# balancingrobot.net
KiCad netlist of a schematic drawn in Altium Designer
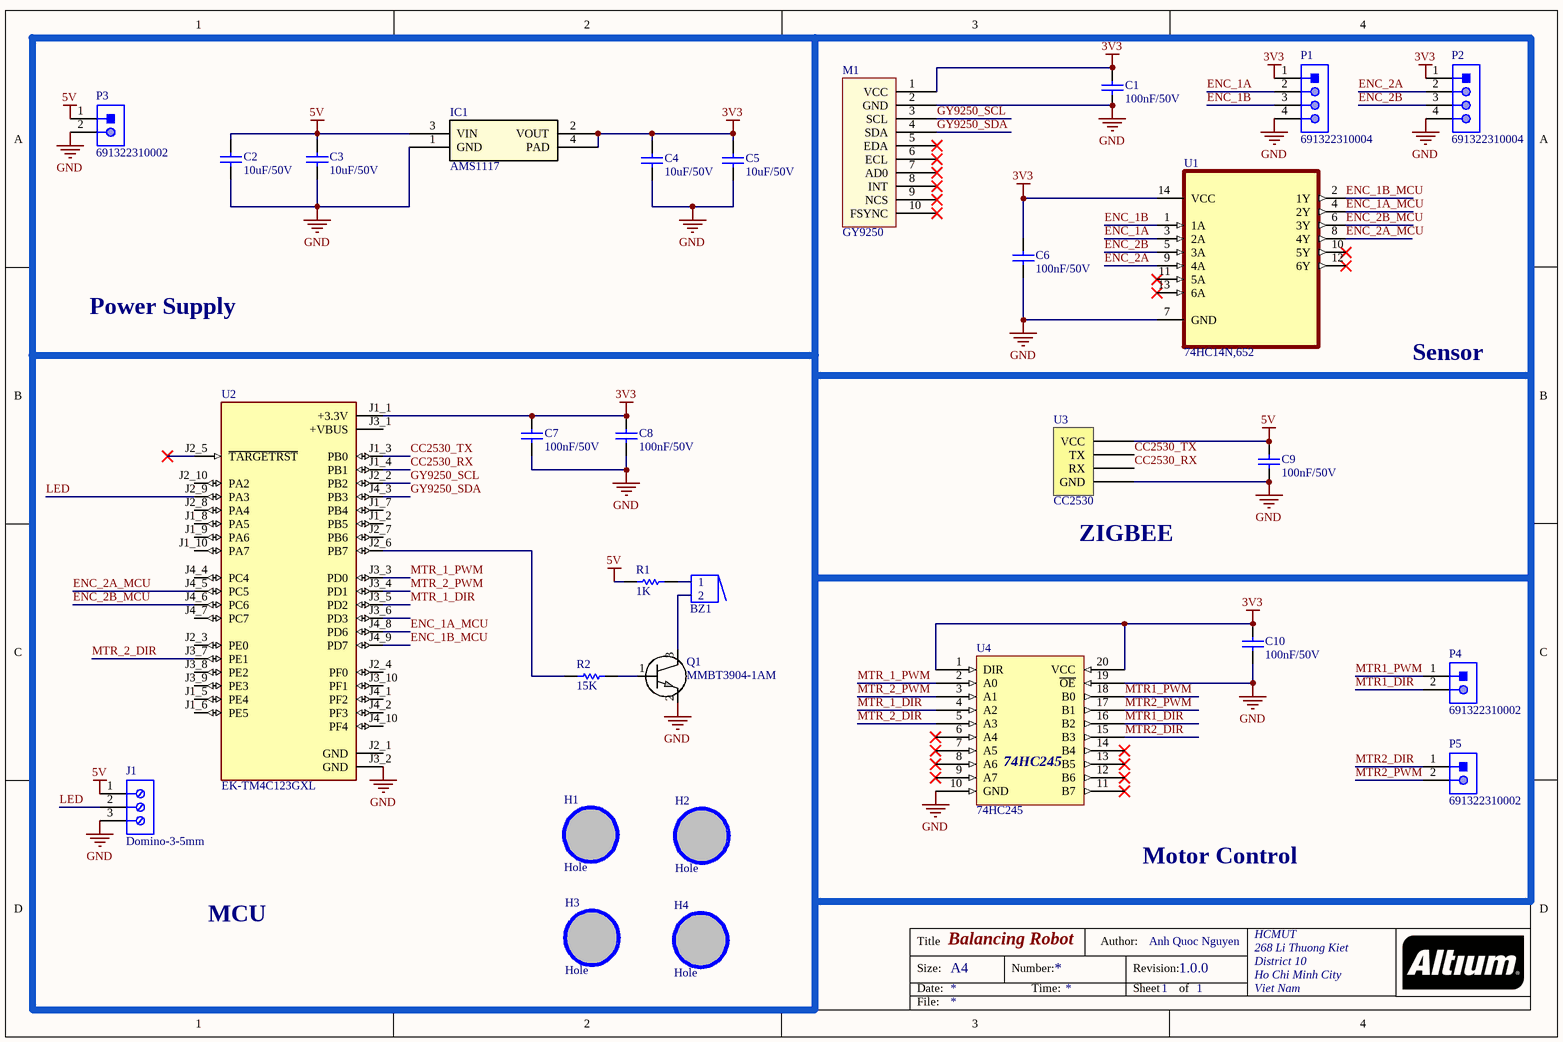
[diagram p0: balancingrobot.SchDoc]

(export (version "E")
  (design (tool "Eeschema 10.0.6"))
  (components
    (comp (ref "BZ1") (value "Buzzer") (footprint "BUZZER") (libsource (lib "xecanbang") (part "Buzzer")))
    (comp (ref "C1")
      (value "100nF/50V")
      (footprint "CAP-SM-0805")
      (description "CAP CER 0.1UF 50V Y5V 0805")
      (fields
        (field (name "MANUFACTURER") "Samsung Electro-Mechanics")
        (field (name "MANUFACTURER PART NUMBER") "CL21F104ZBCNNNC")
      )
      (libsource (lib "Capacitor") (part "Cap-100nF-50V-0805"))
    )
    (comp (ref "C2")
      (value "10uF/50V")
      (footprint "CAP-SM-0805")
      (description "CAP CER 10UF 50V X5R 0805")
      (fields
        (field (name "MANUFACTURER") "Yageo")
        (field (name "MANUFACTURER PART NUMBER") "CC0805KKX5R9BB106")
      )
      (libsource (lib "Capacitor") (part "Cap-10uF-50V-0805"))
    )
    (comp (ref "C3")
      (value "10uF/50V")
      (footprint "CAP-SM-0805")
      (description "CAP CER 10UF 50V X5R 0805")
      (fields
        (field (name "MANUFACTURER") "Yageo")
        (field (name "MANUFACTURER PART NUMBER") "CC0805KKX5R9BB106")
      )
      (libsource (lib "Capacitor") (part "Cap-10uF-50V-0805"))
    )
    (comp (ref "C4")
      (value "10uF/50V")
      (footprint "CAP-SM-0805")
      (description "CAP CER 10UF 50V X5R 0805")
      (fields
        (field (name "MANUFACTURER") "Yageo")
        (field (name "MANUFACTURER PART NUMBER") "CC0805KKX5R9BB106")
      )
      (libsource (lib "Capacitor") (part "Cap-10uF-50V-0805"))
    )
    (comp (ref "C5")
      (value "10uF/50V")
      (footprint "CAP-SM-0805")
      (description "CAP CER 10UF 50V X5R 0805")
      (fields
        (field (name "MANUFACTURER") "Yageo")
        (field (name "MANUFACTURER PART NUMBER") "CC0805KKX5R9BB106")
      )
      (libsource (lib "Capacitor") (part "Cap-10uF-50V-0805"))
    )
    (comp (ref "C6")
      (value "100nF/50V")
      (footprint "CAP-SM-0805")
      (description "CAP CER 0.1UF 50V Y5V 0805")
      (fields
        (field (name "MANUFACTURER") "Samsung Electro-Mechanics")
        (field (name "MANUFACTURER PART NUMBER") "CL21F104ZBCNNNC")
      )
      (libsource (lib "Capacitor") (part "Cap-100nF-50V-0805"))
    )
    (comp (ref "C7")
      (value "100nF/50V")
      (footprint "CAP-SM-0805")
      (description "CAP CER 0.1UF 50V Y5V 0805")
      (fields
        (field (name "MANUFACTURER") "Samsung Electro-Mechanics")
        (field (name "MANUFACTURER PART NUMBER") "CL21F104ZBCNNNC")
      )
      (libsource (lib "Capacitor") (part "Cap-100nF-50V-0805"))
    )
    (comp (ref "C8")
      (value "100nF/50V")
      (footprint "CAP-SM-0805")
      (description "CAP CER 0.1UF 50V Y5V 0805")
      (fields
        (field (name "MANUFACTURER") "Samsung Electro-Mechanics")
        (field (name "MANUFACTURER PART NUMBER") "CL21F104ZBCNNNC")
      )
      (libsource (lib "Capacitor") (part "Cap-100nF-50V-0805"))
    )
    (comp (ref "C9")
      (value "100nF/50V")
      (footprint "CAP-SM-0805")
      (description "CAP CER 0.1UF 50V Y5V 0805")
      (fields
        (field (name "MANUFACTURER") "Samsung Electro-Mechanics")
        (field (name "MANUFACTURER PART NUMBER") "CL21F104ZBCNNNC")
      )
      (libsource (lib "Capacitor") (part "Cap-100nF-50V-0805"))
    )
    (comp (ref "C10")
      (value "100nF/50V")
      (footprint "CAP-SM-0805")
      (description "CAP CER 0.1UF 50V Y5V 0805")
      (fields
        (field (name "MANUFACTURER") "Samsung Electro-Mechanics")
        (field (name "MANUFACTURER PART NUMBER") "CL21F104ZBCNNNC")
      )
      (libsource (lib "Capacitor") (part "Cap-100nF-50V-0805"))
    )
    (comp (ref "H1")
      (value "Hole")
      (footprint "LO KHOAN 3MM")
      (description "Hole 3mm")
      (libsource (lib "PIF_C16_lib") (part "Hole"))
    )
    (comp (ref "H2")
      (value "Hole")
      (footprint "LO KHOAN 3MM")
      (description "Hole 3mm")
      (libsource (lib "PIF_C16_lib") (part "Hole"))
    )
    (comp (ref "H3")
      (value "Hole")
      (footprint "LO KHOAN 3MM")
      (description "Hole 3mm")
      (libsource (lib "PIF_C16_lib") (part "Hole"))
    )
    (comp (ref "H4")
      (value "Hole")
      (footprint "LO KHOAN 3MM")
      (description "Hole 3mm")
      (libsource (lib "PIF_C16_lib") (part "Hole"))
    )
    (comp (ref "IC1")
      (value "AMS1117")
      (footprint "SOT223_AMS111700")
      (fields
        (field (name "MANUFACTURER_PART_NUMBER") "AMS1117-5.0")
        (field (name "COPYRIGHT") "Copyright (C) 2018 Accelerated Designs. All rights reserved")
      )
      (libsource (lib "balancing") (part "AMS1117"))
    )
    (comp (ref "J1")
      (value "Domino-3-5mm")
      (footprint "DOMINO-3-5mm")
      (description "WR-TBL Serie 1347 Horizontal Cable Entry, Pressure Clamp, pitch 5mm, 3p")
      (fields (field (name "PART NUMBER") "691134710003") (field (name "PUBLISHER") "Wurth Elektronik"))
      (libsource (lib "Header-connector") (part "Domino-3-5mm"))
    )
    (comp (ref "M1") (value "GY9250") (footprint "GY9250") (libsource (lib "balancing") (part "GY9250")))
    (comp (ref "P1")
      (value "691322310004")
      (footprint "691322310004")
      (description "WR-TBL Serie 322 Horizontal PCB Header, Pluggable, pitch 3.81mm, 4p")
      (fields (field (name "PUBLISHER") "Wurth Elektronik"))
      (libsource (lib "691322310002.") (part "691322310004"))
    )
    (comp (ref "P2")
      (value "691322310004")
      (footprint "691322310004")
      (description "WR-TBL Serie 322 Horizontal PCB Header, Pluggable, pitch 3.81mm, 4p")
      (fields (field (name "PUBLISHER") "Wurth Elektronik"))
      (libsource (lib "691322310002.") (part "691322310004"))
    )
    (comp (ref "P3")
      (value "691322310002")
      (footprint "691322310002")
      (description "WR-TBL Serie 322 Horizontal PCB Header, Pluggable, pitch 3.81mm, 2p")
      (fields (field (name "PUBLISHER") "Wurth Elektronik"))
      (libsource (lib "691322310002.") (part "691322310002"))
    )
    (comp (ref "P4")
      (value "691322310002")
      (footprint "691322310002")
      (description "WR-TBL Serie 322 Horizontal PCB Header, Pluggable, pitch 3.81mm, 2p")
      (fields (field (name "PUBLISHER") "Wurth Elektronik"))
      (libsource (lib "691322310002.") (part "691322310002"))
    )
    (comp (ref "P5")
      (value "691322310002")
      (footprint "691322310002")
      (description "WR-TBL Serie 322 Horizontal PCB Header, Pluggable, pitch 3.81mm, 2p")
      (fields (field (name "PUBLISHER") "Wurth Elektronik"))
      (libsource (lib "691322310002.") (part "691322310002"))
    )
    (comp (ref "Q1")
      (value "MMBT3904-1AM")
      (footprint "SOT23_NEX")
      (fields
        (field (name "MANUFACTURER_PART_NUMBER") "MMBT3904")
        (field (name "COPYRIGHT") "Copyright (C) 2016 Accelerated Designs. All rights reserved")
      )
      (libsource (lib "xecanbang") (part "MMBT3904-1AM"))
    )
    (comp (ref "R1")
      (value "1K")
      (footprint "Resistor:RES-SM-0805")
      (description "RES 1K OHM 1% 1/4W 0805")
      (fields
        (field (name "MANUFACTURER") "Stackpole Electronics Inc")
        (field (name "MANUFACTURER PART NUMBER") "RNCP0805FTD1K00")
      )
      (libsource (lib "Resistor") (part "Res-1K-0805"))
    )
    (comp (ref "R2")
      (value "15K")
      (footprint "Resistor:RES-SM-0805")
      (description "RES 15K OHM 1% 1/4W 0805")
      (fields
        (field (name "MANUFACTURER") "TE Connectivity Passive Product")
        (field (name "MANUFACTURER PART NUMBER") "CRGCQ0805F15K")
      )
      (libsource (lib "Resistor") (part "Res-15K-0805"))
    )
    (comp (ref "U1")
      (value "74HC14N,652")
      (footprint "DIP254P762X420-14")
      (description "Inverter IC 6 Channel Schmitt Trigger 14-DIP")
      (fields (field (name "MF") "NXP USA"))
      (libsource (lib "74HC14N_652") (part "74HC14N,652"))
    )
    (comp (ref "U2")
      (value "EK-TM4C123GXL")
      (footprint "MODULE_EK-TM4C123GXL")
      (description "ARMÂ® CortexÂ®-M4F Based MCU TM4C123G LaunchPadâ„¢ Evaluation Kit")
      (fields (field (name "MF") "Texas Instruments"))
      (libsource (lib "balancing") (part "EK-TM4C123GXL"))
    )
    (comp (ref "U3")
      (value "CC2530")
      (footprint "CC2530")
      (description "Zigbee")
      (libsource (lib "balancing") (part "Zigbee CC2530"))
    )
    (comp (ref "U4")
      (value "74HC245")
      (footprint "dip20")
      (description "Dán")
      (libsource (lib "THU VIEN SCH") (part "74HC245"))
    )
  )
  (nets
    (net (code "1") (name "/CC2530_RX") (class "Default")
      (node (ref "U2") (pin "J1_4") (pinfunction "PB1_J1_4") (pintype "bidirectional"))
      (node (ref "U3") (pin "3") (pinfunction "RX_3") (pintype "passive"))
    )
    (net (code "2") (name "/CC2530_TX") (class "Default")
      (node (ref "U2") (pin "J1_3") (pinfunction "PB0_J1_3") (pintype "bidirectional"))
      (node (ref "U3") (pin "2") (pinfunction "TX_2") (pintype "passive"))
    )
    (net (code "3") (name "/ENC_1A") (class "Default")
      (node (ref "P1") (pin "2") (pinfunction "2_2") (pintype "passive"))
      (node (ref "U1") (pin "3") (pinfunction "2A_3") (pintype "input"))
    )
    (net (code "4") (name "/ENC_1A_MCU") (class "Default")
      (node (ref "U1") (pin "4") (pinfunction "2Y_4") (pintype "output"))
      (node (ref "U2") (pin "J4_8") (pinfunction "PD6_J4_8") (pintype "bidirectional"))
    )
    (net (code "5") (name "/ENC_1B") (class "Default")
      (node (ref "P1") (pin "3") (pinfunction "3_3") (pintype "passive"))
      (node (ref "U1") (pin "1") (pinfunction "1A_1") (pintype "input"))
    )
    (net (code "6") (name "/ENC_1B_MCU") (class "Default")
      (node (ref "U1") (pin "2") (pinfunction "1Y_2") (pintype "output"))
      (node (ref "U2") (pin "J4_9") (pinfunction "PD7_J4_9") (pintype "bidirectional"))
    )
    (net (code "7") (name "/ENC_2A") (class "Default")
      (node (ref "P2") (pin "2") (pinfunction "2_2") (pintype "passive"))
      (node (ref "U1") (pin "9") (pinfunction "4A_9") (pintype "input"))
    )
    (net (code "8") (name "/ENC_2A_MCU") (class "Default")
      (node (ref "U1") (pin "8") (pinfunction "4Y_8") (pintype "output"))
      (node (ref "U2") (pin "J4_5") (pinfunction "PC5_J4_5") (pintype "bidirectional"))
    )
    (net (code "9") (name "/ENC_2B") (class "Default")
      (node (ref "P2") (pin "3") (pinfunction "3_3") (pintype "passive"))
      (node (ref "U1") (pin "5") (pinfunction "3A_5") (pintype "input"))
    )
    (net (code "10") (name "/ENC_2B_MCU") (class "Default")
      (node (ref "U1") (pin "6") (pinfunction "3Y_6") (pintype "output"))
      (node (ref "U2") (pin "J4_6") (pinfunction "PC6_J4_6") (pintype "bidirectional"))
    )
    (net (code "11") (name "/GY9250_SCL") (class "Default")
      (node (ref "M1") (pin "3") (pinfunction "SCL_3") (pintype "passive"))
      (node (ref "U2") (pin "J2_2") (pinfunction "PB2_J2_2") (pintype "bidirectional"))
    )
    (net (code "12") (name "/GY9250_SDA") (class "Default")
      (node (ref "M1") (pin "4") (pinfunction "SDA_4") (pintype "passive"))
      (node (ref "U2") (pin "J4_3") (pinfunction "PB3_J4_3") (pintype "bidirectional"))
    )
    (net (code "13") (name "/LED") (class "Default")
      (node (ref "J1") (pin "2") (pinfunction "2_2") (pintype "passive"))
      (node (ref "U2") (pin "J2_9") (pinfunction "PA3_J2_9") (pintype "bidirectional"))
    )
    (net (code "14") (name "/MTR1_DIR") (class "Default")
      (node (ref "P4") (pin "2") (pinfunction "2_2") (pintype "passive"))
      (node (ref "U4") (pin "16") (pinfunction "B2_16") (pintype "output"))
    )
    (net (code "15") (name "/MTR1_PWM") (class "Default")
      (node (ref "P4") (pin "1") (pinfunction "1_1") (pintype "passive"))
      (node (ref "U4") (pin "18") (pinfunction "B0_18") (pintype "output"))
    )
    (net (code "16") (name "/MTR2_DIR") (class "Default")
      (node (ref "P5") (pin "1") (pinfunction "1_1") (pintype "passive"))
      (node (ref "U4") (pin "15") (pinfunction "B3_15") (pintype "output"))
    )
    (net (code "17") (name "/MTR2_PWM") (class "Default")
      (node (ref "P5") (pin "2") (pinfunction "2_2") (pintype "passive"))
      (node (ref "U4") (pin "17") (pinfunction "B1_17") (pintype "output"))
    )
    (net (code "18") (name "/MTR_1_DIR") (class "Default")
      (node (ref "U2") (pin "J3_5") (pinfunction "PD2_J3_5") (pintype "bidirectional"))
      (node (ref "U4") (pin "4") (pinfunction "A2_4") (pintype "input"))
    )
    (net (code "19") (name "/MTR_1_PWM") (class "Default")
      (node (ref "U2") (pin "J3_3") (pinfunction "PD0_J3_3") (pintype "bidirectional"))
      (node (ref "U4") (pin "2") (pinfunction "A0_2") (pintype "input"))
    )
    (net (code "20") (name "/MTR_2_DIR") (class "Default")
      (node (ref "U2") (pin "J3_7") (pinfunction "PE1_J3_7") (pintype "bidirectional"))
      (node (ref "U4") (pin "5") (pinfunction "A3_5") (pintype "input"))
    )
    (net (code "21") (name "/MTR_2_PWM") (class "Default")
      (node (ref "U2") (pin "J3_4") (pinfunction "PD1_J3_4") (pintype "bidirectional"))
      (node (ref "U4") (pin "3") (pinfunction "A1_3") (pintype "input"))
    )
    (net (code "22") (name "3V3") (class "Default")
      (node (ref "C1") (pin "2") (pinfunction "2_2") (pintype "passive"))
      (node (ref "C10") (pin "2") (pinfunction "2_2") (pintype "passive"))
      (node (ref "C4") (pin "2") (pinfunction "2_2") (pintype "passive"))
      (node (ref "C5") (pin "2") (pinfunction "2_2") (pintype "passive"))
      (node (ref "C6") (pin "2") (pinfunction "2_2") (pintype "passive"))
      (node (ref "C7") (pin "2") (pinfunction "2_2") (pintype "passive"))
      (node (ref "C8") (pin "2") (pinfunction "2_2") (pintype "passive"))
      (node (ref "IC1") (pin "2") (pinfunction "VOUT_2") (pintype "passive"))
      (node (ref "IC1") (pin "4") (pinfunction "PAD_4") (pintype "passive"))
      (node (ref "M1") (pin "1") (pinfunction "VCC_1") (pintype "passive"))
      (node (ref "P1") (pin "1") (pinfunction "1_1") (pintype "passive"))
      (node (ref "P2") (pin "1") (pinfunction "1_1") (pintype "passive"))
      (node (ref "U1") (pin "14") (pinfunction "VCC_14") (pintype "power_in"))
      (node (ref "U2") (pin "J1_1") (pinfunction "+3.3V_J1_1") (pintype "power_in"))
      (node (ref "U4") (pin "1") (pinfunction "DIR_1") (pintype "input"))
      (node (ref "U4") (pin "20") (pinfunction "VCC_20") (pintype "input"))
    )
    (net (code "23") (name "5V") (class "Default")
      (node (ref "C2") (pin "2") (pinfunction "2_2") (pintype "passive"))
      (node (ref "C3") (pin "2") (pinfunction "2_2") (pintype "passive"))
      (node (ref "C9") (pin "2") (pinfunction "2_2") (pintype "passive"))
      (node (ref "IC1") (pin "3") (pinfunction "VIN_3") (pintype "passive"))
      (node (ref "J1") (pin "1") (pinfunction "1_1") (pintype "passive"))
      (node (ref "P3") (pin "1") (pinfunction "1_1") (pintype "passive"))
      (node (ref "R1") (pin "2") (pinfunction "2_2") (pintype "passive"))
      (node (ref "U3") (pin "1") (pinfunction "VCC_1") (pintype "passive"))
    )
    (net (code "24") (name "GND") (class "Default")
      (node (ref "C1") (pin "1") (pinfunction "1_1") (pintype "passive"))
      (node (ref "C10") (pin "1") (pinfunction "1_1") (pintype "passive"))
      (node (ref "C2") (pin "1") (pinfunction "1_1") (pintype "passive"))
      (node (ref "C3") (pin "1") (pinfunction "1_1") (pintype "passive"))
      (node (ref "C4") (pin "1") (pinfunction "1_1") (pintype "passive"))
      (node (ref "C5") (pin "1") (pinfunction "1_1") (pintype "passive"))
      (node (ref "C6") (pin "1") (pinfunction "1_1") (pintype "passive"))
      (node (ref "C7") (pin "1") (pinfunction "1_1") (pintype "passive"))
      (node (ref "C8") (pin "1") (pinfunction "1_1") (pintype "passive"))
      (node (ref "C9") (pin "1") (pinfunction "1_1") (pintype "passive"))
      (node (ref "IC1") (pin "1") (pinfunction "GND_1") (pintype "passive"))
      (node (ref "J1") (pin "3") (pinfunction "3_3") (pintype "passive"))
      (node (ref "M1") (pin "2") (pinfunction "GND_2") (pintype "passive"))
      (node (ref "P1") (pin "4") (pinfunction "4_4") (pintype "passive"))
      (node (ref "P2") (pin "4") (pinfunction "4_4") (pintype "passive"))
      (node (ref "P3") (pin "2") (pinfunction "2_2") (pintype "passive"))
      (node (ref "Q1") (pin "2") (pinfunction "2_2") (pintype "passive"))
      (node (ref "U1") (pin "7") (pinfunction "GND_7") (pintype "passive"))
      (node (ref "U2") (pin "J3_2") (pinfunction "GND_J3_2") (pintype "power_in"))
      (node (ref "U3") (pin "4") (pinfunction "GND_4") (pintype "passive"))
      (node (ref "U4") (pin "10") (pinfunction "GND_10") (pintype "input"))
      (node (ref "U4") (pin "19") (pinfunction "~{OE}_19") (pintype "input"))
    )
    (net (code "25") (name "Net-(BZ1-Pad1)") (class "Default")
      (node (ref "BZ1") (pin "1") (pinfunction "1_1") (pintype "passive"))
      (node (ref "R1") (pin "1") (pinfunction "1_1") (pintype "passive"))
    )
    (net (code "26") (name "Net-(BZ1-Pad2)") (class "Default")
      (node (ref "BZ1") (pin "2") (pinfunction "2_2") (pintype "passive"))
      (node (ref "Q1") (pin "3") (pinfunction "3_3") (pintype "passive"))
    )
    (net (code "27") (name "Net-(Q1-Pad1)") (class "Default")
      (node (ref "Q1") (pin "1") (pinfunction "1_1") (pintype "passive"))
      (node (ref "R2") (pin "2") (pinfunction "2_2") (pintype "passive"))
    )
    (net (code "28") (name "Net-(U2-PB7)") (class "Default")
      (node (ref "R2") (pin "1") (pinfunction "1_1") (pintype "passive"))
      (node (ref "U2") (pin "J2_6") (pinfunction "PB7_J2_6") (pintype "bidirectional"))
    )
    (net (code "29") (name "unconnected-(H1-Pad1)") (class "Default")
      (node (ref "H1") (pin "1") (pinfunction "1_1") (pintype "passive"))
    )
    (net (code "30") (name "unconnected-(H2-Pad1)") (class "Default")
      (node (ref "H2") (pin "1") (pinfunction "1_1") (pintype "passive"))
    )
    (net (code "31") (name "unconnected-(H3-Pad1)") (class "Default")
      (node (ref "H3") (pin "1") (pinfunction "1_1") (pintype "passive"))
    )
    (net (code "32") (name "unconnected-(H4-Pad1)") (class "Default")
      (node (ref "H4") (pin "1") (pinfunction "1_1") (pintype "passive"))
    )
    (net (code "33") (name "unconnected-(M1-AD0-Pad7)") (class "Default")
      (node (ref "M1") (pin "7") (pinfunction "AD0_7") (pintype "passive+no_connect"))
    )
    (net (code "34") (name "unconnected-(M1-ECL-Pad6)") (class "Default")
      (node (ref "M1") (pin "6") (pinfunction "ECL_6") (pintype "passive+no_connect"))
    )
    (net (code "35") (name "unconnected-(M1-EDA-Pad5)") (class "Default")
      (node (ref "M1") (pin "5") (pinfunction "EDA_5") (pintype "passive+no_connect"))
    )
    (net (code "36") (name "unconnected-(M1-FSYNC-Pad10)") (class "Default")
      (node (ref "M1") (pin "10") (pinfunction "FSYNC_10") (pintype "passive+no_connect"))
    )
    (net (code "37") (name "unconnected-(M1-INT-Pad8)") (class "Default")
      (node (ref "M1") (pin "8") (pinfunction "INT_8") (pintype "passive+no_connect"))
    )
    (net (code "38") (name "unconnected-(M1-NCS-Pad9)") (class "Default")
      (node (ref "M1") (pin "9") (pinfunction "NCS_9") (pintype "passive+no_connect"))
    )
    (net (code "39") (name "unconnected-(U1-5A-Pad11)") (class "Default")
      (node (ref "U1") (pin "11") (pinfunction "5A_11") (pintype "input+no_connect"))
    )
    (net (code "40") (name "unconnected-(U1-5Y-Pad10)") (class "Default")
      (node (ref "U1") (pin "10") (pinfunction "5Y_10") (pintype "output+no_connect"))
    )
    (net (code "41") (name "unconnected-(U1-6A-Pad13)") (class "Default")
      (node (ref "U1") (pin "13") (pinfunction "6A_13") (pintype "input+no_connect"))
    )
    (net (code "42") (name "unconnected-(U1-6Y-Pad12)") (class "Default")
      (node (ref "U1") (pin "12") (pinfunction "6Y_12") (pintype "output+no_connect"))
    )
    (net (code "43") (name "unconnected-(U2-+VBUS-PadJ3_1)") (class "Default")
      (node (ref "U2") (pin "J3_1") (pinfunction "+VBUS_J3_1") (pintype "power_in"))
    )
    (net (code "44") (name "unconnected-(U2-GND-PadJ2_1)") (class "Default")
      (node (ref "U2") (pin "J2_1") (pinfunction "GND_J2_1") (pintype "power_in"))
    )
    (net (code "45") (name "unconnected-(U2-PA2-PadJ2_10)") (class "Default")
      (node (ref "U2") (pin "J2_10") (pinfunction "PA2_J2_10") (pintype "bidirectional"))
    )
    (net (code "46") (name "unconnected-(U2-PA4-PadJ2_8)") (class "Default")
      (node (ref "U2") (pin "J2_8") (pinfunction "PA4_J2_8") (pintype "bidirectional"))
    )
    (net (code "47") (name "unconnected-(U2-PA5-PadJ1_8)") (class "Default")
      (node (ref "U2") (pin "J1_8") (pinfunction "PA5_J1_8") (pintype "bidirectional"))
    )
    (net (code "48") (name "unconnected-(U2-PA6-PadJ1_9)") (class "Default")
      (node (ref "U2") (pin "J1_9") (pinfunction "PA6_J1_9") (pintype "bidirectional"))
    )
    (net (code "49") (name "unconnected-(U2-PA7-PadJ1_10)") (class "Default")
      (node (ref "U2") (pin "J1_10") (pinfunction "PA7_J1_10") (pintype "bidirectional"))
    )
    (net (code "50") (name "unconnected-(U2-PB4-PadJ1_7)") (class "Default")
      (node (ref "U2") (pin "J1_7") (pinfunction "PB4_J1_7") (pintype "bidirectional"))
    )
    (net (code "51") (name "unconnected-(U2-PB5-PadJ1_2)") (class "Default")
      (node (ref "U2") (pin "J1_2") (pinfunction "PB5_J1_2") (pintype "bidirectional"))
    )
    (net (code "52") (name "unconnected-(U2-PB6-PadJ2_7)") (class "Default")
      (node (ref "U2") (pin "J2_7") (pinfunction "PB6_J2_7") (pintype "bidirectional"))
    )
    (net (code "53") (name "unconnected-(U2-PC4-PadJ4_4)") (class "Default")
      (node (ref "U2") (pin "J4_4") (pinfunction "PC4_J4_4") (pintype "bidirectional"))
    )
    (net (code "54") (name "unconnected-(U2-PC7-PadJ4_7)") (class "Default")
      (node (ref "U2") (pin "J4_7") (pinfunction "PC7_J4_7") (pintype "bidirectional"))
    )
    (net (code "55") (name "unconnected-(U2-PD3-PadJ3_6)") (class "Default")
      (node (ref "U2") (pin "J3_6") (pinfunction "PD3_J3_6") (pintype "bidirectional"))
    )
    (net (code "56") (name "unconnected-(U2-PE0-PadJ2_3)") (class "Default")
      (node (ref "U2") (pin "J2_3") (pinfunction "PE0_J2_3") (pintype "bidirectional"))
    )
    (net (code "57") (name "unconnected-(U2-PE2-PadJ3_8)") (class "Default")
      (node (ref "U2") (pin "J3_8") (pinfunction "PE2_J3_8") (pintype "bidirectional"))
    )
    (net (code "58") (name "unconnected-(U2-PE3-PadJ3_9)") (class "Default")
      (node (ref "U2") (pin "J3_9") (pinfunction "PE3_J3_9") (pintype "bidirectional"))
    )
    (net (code "59") (name "unconnected-(U2-PE4-PadJ1_5)") (class "Default")
      (node (ref "U2") (pin "J1_5") (pinfunction "PE4_J1_5") (pintype "bidirectional"))
    )
    (net (code "60") (name "unconnected-(U2-PE5-PadJ1_6)") (class "Default")
      (node (ref "U2") (pin "J1_6") (pinfunction "PE5_J1_6") (pintype "bidirectional"))
    )
    (net (code "61") (name "unconnected-(U2-PF0-PadJ2_4)") (class "Default")
      (node (ref "U2") (pin "J2_4") (pinfunction "PF0_J2_4") (pintype "bidirectional"))
    )
    (net (code "62") (name "unconnected-(U2-PF1-PadJ3_10)") (class "Default")
      (node (ref "U2") (pin "J3_10") (pinfunction "PF1_J3_10") (pintype "bidirectional"))
    )
    (net (code "63") (name "unconnected-(U2-PF2-PadJ4_1)") (class "Default")
      (node (ref "U2") (pin "J4_1") (pinfunction "PF2_J4_1") (pintype "bidirectional"))
    )
    (net (code "64") (name "unconnected-(U2-PF3-PadJ4_2)") (class "Default")
      (node (ref "U2") (pin "J4_2") (pinfunction "PF3_J4_2") (pintype "bidirectional"))
    )
    (net (code "65") (name "unconnected-(U2-PF4-PadJ4_10)") (class "Default")
      (node (ref "U2") (pin "J4_10") (pinfunction "PF4_J4_10") (pintype "bidirectional"))
    )
    (net (code "66") (name "unconnected-(U2-~{TARGETRST}-PadJ2_5)") (class "Default")
      (node (ref "U2") (pin "J2_5") (pinfunction "~{TARGETRST}_J2_5") (pintype "input+no_connect"))
    )
    (net (code "67") (name "unconnected-(U4-A4-Pad6)") (class "Default")
      (node (ref "U4") (pin "6") (pinfunction "A4_6") (pintype "input+no_connect"))
    )
    (net (code "68") (name "unconnected-(U4-A5-Pad7)") (class "Default")
      (node (ref "U4") (pin "7") (pinfunction "A5_7") (pintype "input+no_connect"))
    )
    (net (code "69") (name "unconnected-(U4-A6-Pad8)") (class "Default")
      (node (ref "U4") (pin "8") (pinfunction "A6_8") (pintype "input+no_connect"))
    )
    (net (code "70") (name "unconnected-(U4-A7-Pad9)") (class "Default")
      (node (ref "U4") (pin "9") (pinfunction "A7_9") (pintype "input+no_connect"))
    )
    (net (code "71") (name "unconnected-(U4-B4-Pad14)") (class "Default")
      (node (ref "U4") (pin "14") (pinfunction "B4_14") (pintype "output+no_connect"))
    )
    (net (code "72") (name "unconnected-(U4-B5-Pad13)") (class "Default")
      (node (ref "U4") (pin "13") (pinfunction "B5_13") (pintype "output+no_connect"))
    )
    (net (code "73") (name "unconnected-(U4-B6-Pad12)") (class "Default")
      (node (ref "U4") (pin "12") (pinfunction "B6_12") (pintype "output+no_connect"))
    )
    (net (code "74") (name "unconnected-(U4-B7-Pad11)") (class "Default")
      (node (ref "U4") (pin "11") (pinfunction "B7_11") (pintype "output+no_connect"))
    )
  )
)
